# comutator.net
KiCad netlist of a schematic drawn in Altium Designer
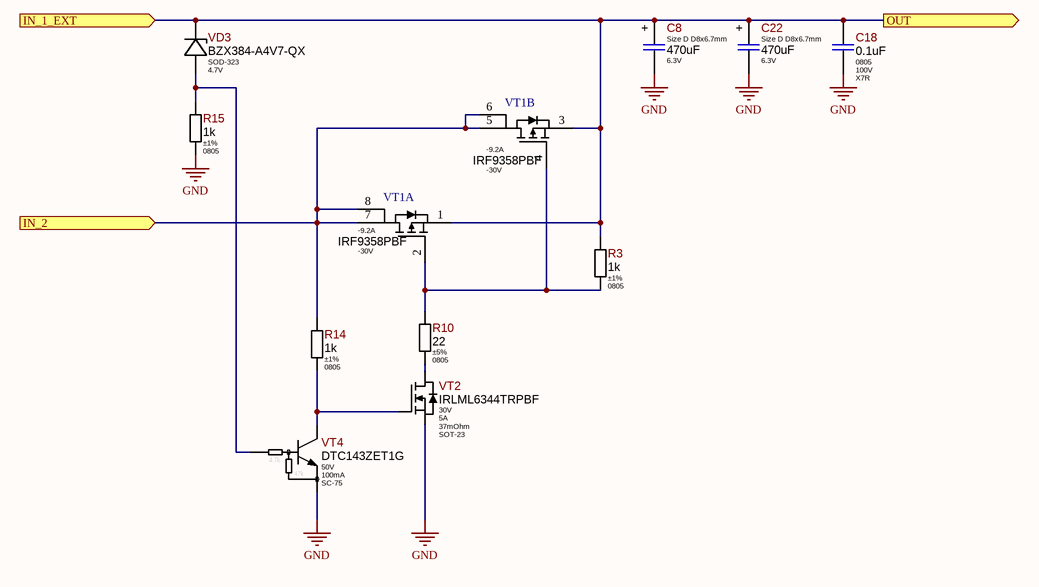
[diagram p0: comutator.SchDoc]

(export (version "E")
  (design (tool "Eeschema 10.0.6"))
  (components
    (comp (ref "C8")
      (value "470uF")
      (footprint "CAP-AE-830x670H30_MED")
      (fields
        (field (name "PACKAGE") "Size D D8x6.7mm")
        (field (name "VOLTAGE") "6.3V")
        (field (name "PART NUMBER") "RHA0J471MCN1GS")
        (field (name "MANUFACTURER") "Nichicon")
        (field (name "TOLERANCE") "±20%")
      )
      (libsource (lib "capacitors") (part "RHA0J471MCN1GS"))
    )
    (comp (ref "C18")
      (value "0.1uF")
      (footprint "C_CERAMIC_0805_MED")
      (description "100nF 100V X7R ±10% 0805 Ceramic Capacitor RoHS")
      (fields
        (field (name "PACKAGE") "0805")
        (field (name "VOLTAGE") "100V")
        (field (name "DIELECTRIC TYPE") "X7R")
        (field (name "PART NUMBER") "CL21B104KCFSFNE")
        (field (name "MANUFACTURER") "Samsung Electro-Mechanics")
      )
      (libsource (lib "capacitors") (part "CL21B104KCFSFNE"))
    )
    (comp (ref "C22")
      (value "470uF")
      (footprint "CAP-AE-830x670H30_MED")
      (fields
        (field (name "PACKAGE") "Size D D8x6.7mm")
        (field (name "VOLTAGE") "6.3V")
        (field (name "PART NUMBER") "RHA0J471MCN1GS")
        (field (name "MANUFACTURER") "Nichicon")
        (field (name "TOLERANCE") "±20%")
      )
      (libsource (lib "capacitors") (part "RHA0J471MCN1GS"))
    )
    (comp (ref "R3")
      (value "1k")
      (footprint "R_ANY_CHIP_0805_MED")
      (description "2.2 kOhms ±1% 1/8W 0805 Thick Film Resistor")
      (fields
        (field (name "TOLERANCE") "±1%")
        (field (name "PACKAGE") "0805")
        (field (name "PART NUMBER") "RC0805FR-072K2L")
        (field (name "MANUFACTURER") "Yageo")
      )
      (libsource (lib "resistors") (part "RC0805FR-072K2L"))
    )
    (comp (ref "R10")
      (value "22")
      (footprint "R_ANY_CHIP_0805_MED")
      (description "22 Ohms ±5%, 1/8W 0805 Thick Film Resistor")
      (fields
        (field (name "TOLERANCE") "±5%")
        (field (name "PACKAGE") "0805")
        (field (name "PART NUMBER") "RC0805JR-0722RL")
        (field (name "MANUFACTURER") "Yageo")
      )
      (libsource (lib "resistors") (part "RC0805JR-0722RL"))
    )
    (comp (ref "R14")
      (value "1k")
      (footprint "R_ANY_CHIP_0805_MED")
      (description "2.2 kOhms ±1% 1/8W 0805 Thick Film Resistor")
      (fields
        (field (name "TOLERANCE") "±1%")
        (field (name "PACKAGE") "0805")
        (field (name "PART NUMBER") "RC0805FR-072K2L")
        (field (name "MANUFACTURER") "Yageo")
      )
      (libsource (lib "resistors") (part "RC0805FR-072K2L"))
    )
    (comp (ref "R15")
      (value "1k")
      (footprint "R_ANY_CHIP_0805_MED")
      (description "2.2 kOhms ±1% 1/8W 0805 Thick Film Resistor")
      (fields
        (field (name "TOLERANCE") "±1%")
        (field (name "PACKAGE") "0805")
        (field (name "PART NUMBER") "RC0805FR-072K2L")
        (field (name "MANUFACTURER") "Yageo")
      )
      (libsource (lib "resistors") (part "RC0805FR-072K2L"))
    )
    (comp (ref "VD3")
      (value "BZX384-A4V7-QX")
      (footprint "SOD-323_MED")
      (description "Zener Diode 4.7V, 300mW, ±1%, Leakage 3uA @ 2V, SOD-323")
      (fields
        (field (name "PART NUMBER") "BZX384-A4V7-QX")
        (field (name "PACKAGE") "SOD-323")
        (field (name "VOLTAGE") "4.7V")
        (field (name "MANUFACTURER") "Nexperia USA")
      )
      (libsource (lib "diodes") (part "BZX384-A4V7-QX"))
    )
    (comp (ref "VT1")
      (value "IRF9358PBF")
      (footprint "FP-PG-DSO-8-IPC_B")
      (description "MOSFET 2P-CH 30V 9.2A 8SOIC")
      (fields
        (field (name "MANUFACTURER") "Infineon Technologies")
        (field (name "OCTOPART") "https://octopart.com/irf9358pbf-infineon-65873752")
        (field (name "CONTINUOUS DRAIN CURRENT") "-9.2A")
        (field (name "MANUFACTURER PART NUMBER") "IRF9358PBF")
        (field (name "DRAIN TO SOURCE VOLTAGE") "-30V")
      )
      (libsource (lib "vitech_lib") (part "IRF9358PbF"))
    )
    (comp (ref "VT2")
      (value "IRLML6344")
      (footprint "SOT-23_MED")
      (description "30V, 5A max N-Channel HEXFET MOSFET, 29mOhm @ Vgs = 4.5V")
      (fields
        (field (name "PART NUMBER") "IRLML6344TRPBF")
        (field (name "VDS") "30V")
        (field (name "ID") "5A")
        (field (name "RDS") "37mOhm")
        (field (name "PACKAGE") "SOT-23")
        (field (name "MANUFACTURER") "Infineon Technologies")
      )
      (libsource (lib "transistors") (part "IRLML6344TRPBF"))
    )
    (comp (ref "VT4")
      (value "DTC143ZET1G")
      (footprint "SOT-416")
      (description "50V, 100mA Low Vce(sat) NPN Digital Transistor, Pre-Biased 4.7k/47k (with built-in resistors)")
      (fields
        (field (name "PART NUMBER") "DTC143ZET1G")
        (field (name "VCE") "50V")
        (field (name "IC") "100mA")
        (field (name "PACKAGE") "SC-75")
        (field (name "MANUFACTURER") "Onsemi")
      )
      (libsource (lib "transistors") (part "DTC143ZET1G"))
    )
  )
  (nets
    (net (code "1") (name "/IN_1_EXT") (class "Default")
      (node (ref "C18") (pin "1") (pinfunction "1_1") (pintype "passive"))
      (node (ref "C22") (pin "1") (pinfunction "1_1") (pintype "passive"))
      (node (ref "C8") (pin "1") (pinfunction "1_1") (pintype "passive"))
      (node (ref "R3") (pin "1") (pintype "passive"))
      (node (ref "VD3") (pin "CA") (pintype "passive"))
      (node (ref "VT1") (pin "1") (pinfunction "S2_1") (pintype "passive"))
      (node (ref "VT1") (pin "3") (pinfunction "S1_3") (pintype "passive"))
    )
    (net (code "2") (name "/IN_2") (class "Default")
      (node (ref "R14") (pin "1") (pintype "passive"))
      (node (ref "VT1") (pin "5") (pinfunction "D12_5") (pintype "passive"))
      (node (ref "VT1") (pin "6") (pinfunction "D11_6") (pintype "passive"))
      (node (ref "VT1") (pin "7") (pinfunction "D22_7") (pintype "passive"))
      (node (ref "VT1") (pin "8") (pinfunction "D21_8") (pintype "passive"))
    )
    (net (code "3") (name "GND") (class "Default")
      (node (ref "C18") (pin "2") (pinfunction "2_2") (pintype "passive"))
      (node (ref "C22") (pin "2") (pinfunction "2_2") (pintype "passive"))
      (node (ref "C8") (pin "2") (pinfunction "2_2") (pintype "passive"))
      (node (ref "R15") (pin "2") (pintype "passive"))
      (node (ref "VT2") (pin "2") (pinfunction "S_2") (pintype "passive"))
      (node (ref "VT4") (pin "2") (pinfunction "E_2") (pintype "passive"))
    )
    (net (code "4") (name "Net-(VT1A-G2)") (class "Default")
      (node (ref "R10") (pin "1") (pintype "passive"))
      (node (ref "R3") (pin "2") (pintype "passive"))
      (node (ref "VT1") (pin "2") (pinfunction "G2_2") (pintype "passive"))
      (node (ref "VT1") (pin "4") (pinfunction "G1_4") (pintype "passive"))
    )
    (net (code "5") (name "Net-(VT2-D)") (class "Default")
      (node (ref "R10") (pin "2") (pintype "passive"))
      (node (ref "VT2") (pin "3") (pinfunction "D_3") (pintype "passive"))
    )
    (net (code "6") (name "Net-(VT2-G)") (class "Default")
      (node (ref "R14") (pin "2") (pintype "passive"))
      (node (ref "VT2") (pin "1") (pinfunction "G_1") (pintype "passive"))
      (node (ref "VT4") (pin "3") (pinfunction "C_3") (pintype "passive"))
    )
    (net (code "7") (name "Net-(VT4-B)") (class "Default")
      (node (ref "R15") (pin "1") (pintype "passive"))
      (node (ref "VD3") (pin "AN") (pintype "passive"))
      (node (ref "VT4") (pin "1") (pinfunction "B_1") (pintype "passive"))
    )
  )
)
